# Regulador.net
KiCad netlist of a schematic drawn in Altium Designer
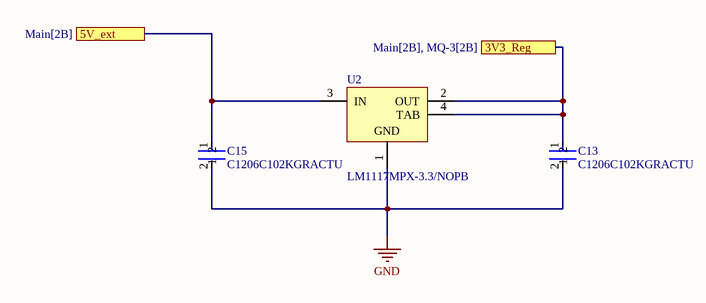
[diagram p0: Regulador.SchDoc]

(export (version "E")
  (design (tool "Eeschema 10.0.6"))
  (components
    (comp (ref "C13")
      (value "C1206C102KGRACTU")
      (footprint "FP-C1206C-EF-IPC_A")
      (description "CAP CER 1000PF 2KV X7R 1206")
      (fields (field (name "VOLTAGE") "2kV") (field (name "TOLERANCE") "10%"))
      (libsource (lib "Altium Content Vault") (part "b4654b650e69147ec39a6b967a45e02"))
    )
    (comp (ref "C15")
      (value "C1206C102KGRACTU")
      (footprint "FP-C1206C-EF-IPC_A")
      (description "CAP CER 1000PF 2KV X7R 1206")
      (fields (field (name "VOLTAGE") "2kV") (field (name "TOLERANCE") "10%"))
      (libsource (lib "Altium Content Vault") (part "b4654b650e69147ec39a6b967a45e02"))
    )
    (comp (ref "U2")
      (value "LM1117MPX-3.3/NOPB")
      (footprint "DCY0004A_L")
      (description "800mA Low-Dropout Linear Regulator, 4-pin SOT-223, Pb-Free")
      (fields (field (name "MANUFACTURER") "Texas Instruments"))
      (libsource (lib "Altium Content Vault") (part "PM-REG-LM1086-SOT4"))
    )
  )
  (nets
    (net (code "1") (name "/3V3_Reg") (class "Default")
      (node (ref "C13") (pin "1") (pinfunction "1_1") (pintype "passive"))
      (node (ref "U2") (pin "2") (pinfunction "OUT_2") (pintype "power_in"))
      (node (ref "U2") (pin "4") (pinfunction "TAB_4") (pintype "power_in"))
    )
    (net (code "2") (name "/5V_ext") (class "Default")
      (node (ref "C15") (pin "1") (pinfunction "1_1") (pintype "passive"))
      (node (ref "U2") (pin "3") (pinfunction "IN_3") (pintype "power_in"))
    )
    (net (code "3") (name "GND") (class "Default")
      (node (ref "C13") (pin "2") (pinfunction "2_2") (pintype "passive"))
      (node (ref "C15") (pin "2") (pinfunction "2_2") (pintype "passive"))
      (node (ref "U2") (pin "1") (pinfunction "GND_1") (pintype "power_in"))
    )
  )
)
